# ADE7753Schematic-ATMEGA.net
KiCad netlist of a schematic drawn in EAGLE
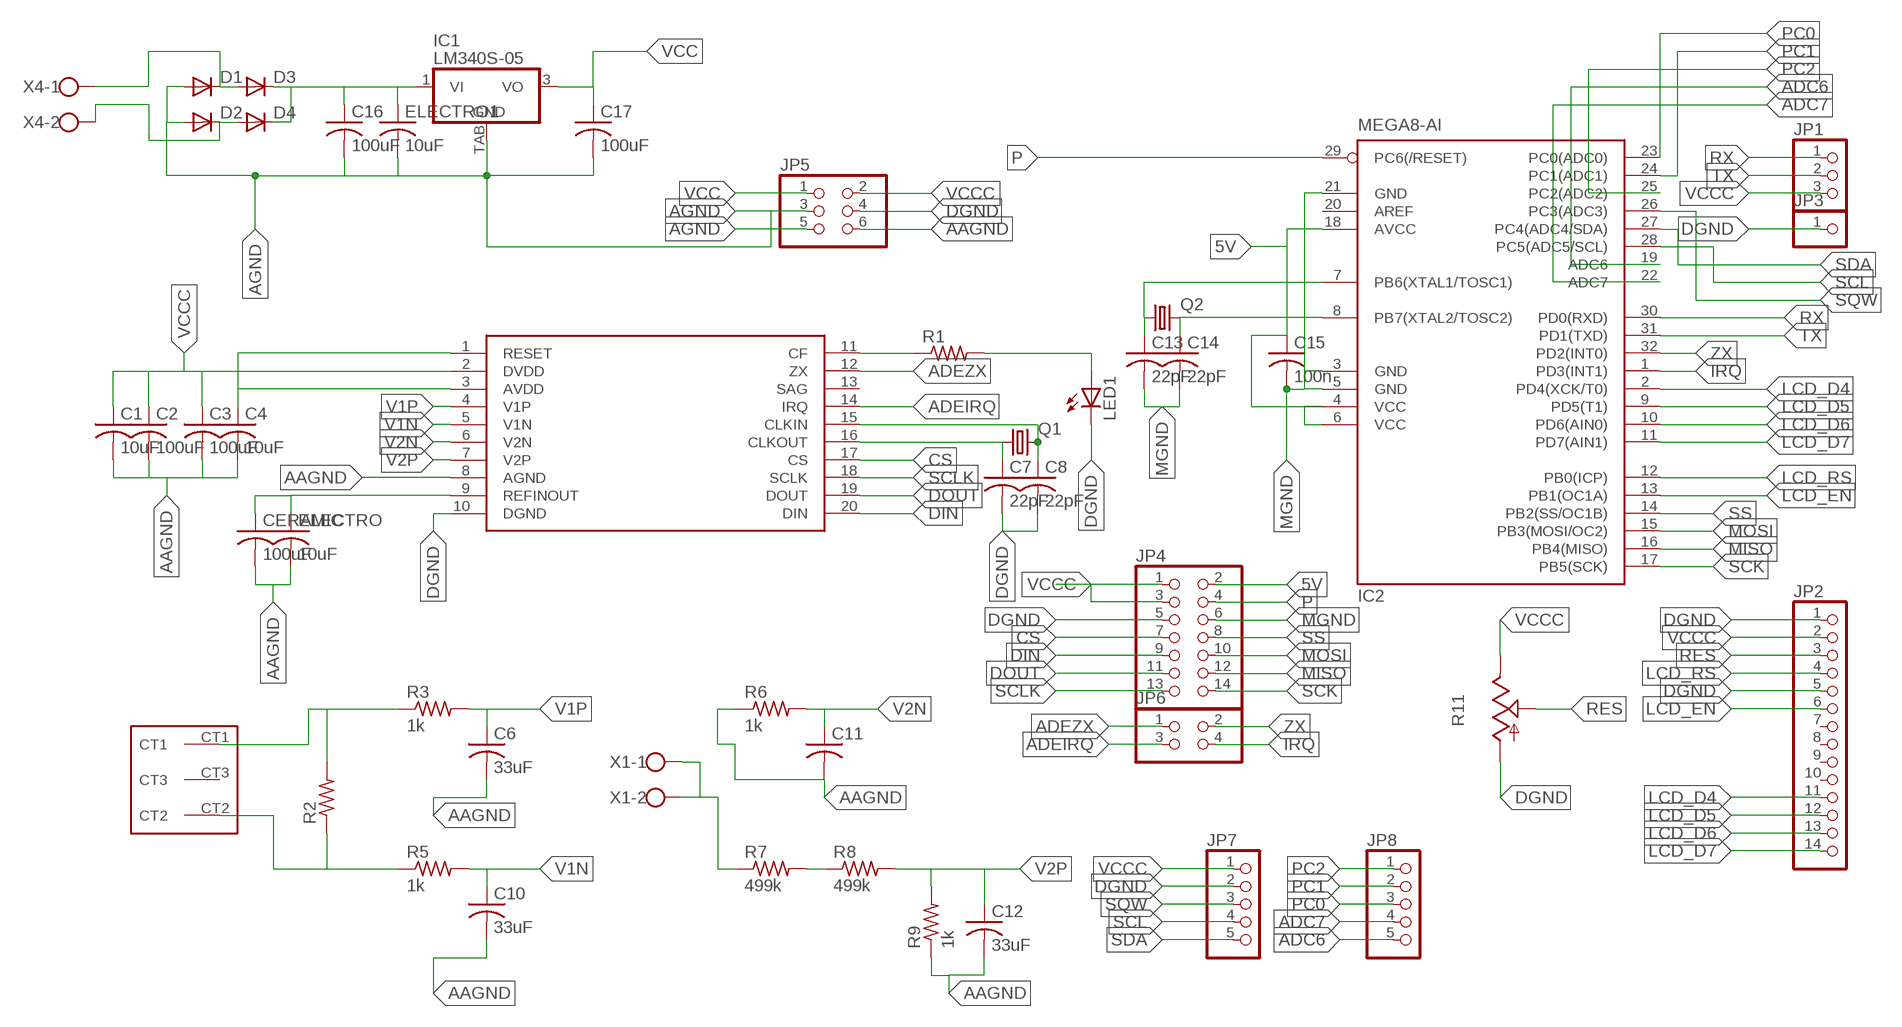
[diagram p0: schematic, sheet 1]

(export (version "E")
  (design (tool "Eeschema 10.0.6"))
  (components
    (comp (ref "C1")
      (value "10uF")
      (footprint "eagle-import:C025-030X050")
      (libsource (lib "eagle-import") (part "C-US025-030X050"))
    )
    (comp (ref "C2")
      (value "100uF")
      (footprint "eagle-import:C0603K")
      (libsource (lib "eagle-import") (part "C-USC0603K"))
    )
    (comp (ref "C3")
      (value "100uF")
      (footprint "eagle-import:C0603K")
      (libsource (lib "eagle-import") (part "C-USC0603K"))
    )
    (comp (ref "C4")
      (value "10uF")
      (footprint "eagle-import:C025-030X050")
      (libsource (lib "eagle-import") (part "C-US025-030X050"))
    )
    (comp (ref "C6")
      (value "33uF")
      (footprint "eagle-import:C0805K")
      (libsource (lib "eagle-import") (part "C-USC0805K"))
    )
    (comp (ref "C7")
      (value "22pF")
      (footprint "eagle-import:C0603K")
      (libsource (lib "eagle-import") (part "C-USC0603K"))
    )
    (comp (ref "C8")
      (value "22pF")
      (footprint "eagle-import:C0603K")
      (libsource (lib "eagle-import") (part "C-USC0603K"))
    )
    (comp (ref "C10")
      (value "33uF")
      (footprint "eagle-import:C0805K")
      (libsource (lib "eagle-import") (part "C-USC0805K"))
    )
    (comp (ref "C11")
      (value "C-USC0805K")
      (footprint "eagle-import:C0805K")
      (libsource (lib "eagle-import") (part "C-USC0805K"))
    )
    (comp (ref "C12")
      (value "33uF")
      (footprint "eagle-import:C0805K")
      (libsource (lib "eagle-import") (part "C-USC0805K"))
    )
    (comp (ref "C13")
      (value "22pF")
      (footprint "eagle-import:C0603K")
      (libsource (lib "eagle-import") (part "C-USC0603K"))
    )
    (comp (ref "C14")
      (value "22pF")
      (footprint "eagle-import:C0603K")
      (libsource (lib "eagle-import") (part "C-USC0603K"))
    )
    (comp (ref "C15")
      (value "100n")
      (footprint "eagle-import:C0603K")
      (libsource (lib "eagle-import") (part "C-USC0603K"))
    )
    (comp (ref "C16")
      (value "100uF")
      (footprint "eagle-import:C0603K")
      (libsource (lib "eagle-import") (part "C-USC0603K"))
    )
    (comp (ref "C17")
      (value "100uF")
      (footprint "eagle-import:C0603K")
      (libsource (lib "eagle-import") (part "C-USC0603K"))
    )
    (comp (ref "CERAMIC")
      (value "100uF")
      (footprint "eagle-import:C0603K")
      (libsource (lib "eagle-import") (part "C-USC0603K"))
    )
    (comp (ref "D1")
      (value "DIODE-SMB")
      (footprint "eagle-import:SMB")
      (libsource (lib "eagle-import") (part "DIODE-SMB"))
    )
    (comp (ref "D2")
      (value "DIODE-SMB")
      (footprint "eagle-import:SMB")
      (libsource (lib "eagle-import") (part "DIODE-SMB"))
    )
    (comp (ref "D3")
      (value "DIODE-SMB")
      (footprint "eagle-import:SMB")
      (libsource (lib "eagle-import") (part "DIODE-SMB"))
    )
    (comp (ref "D4")
      (value "DIODE-SMB")
      (footprint "eagle-import:SMB")
      (libsource (lib "eagle-import") (part "DIODE-SMB"))
    )
    (comp (ref "ELECTRO")
      (value "10uF")
      (footprint "eagle-import:C025-030X050")
      (libsource (lib "eagle-import") (part "C-US025-030X050"))
    )
    (comp (ref "ELECTRO1")
      (value "10uF")
      (footprint "eagle-import:C025-030X050")
      (libsource (lib "eagle-import") (part "C-US025-030X050"))
    )
    (comp (ref "IC1")
      (value "LM340S-05")
      (footprint "eagle-import:TO263-3")
      (libsource (lib "eagle-import") (part "LM340?-S05"))
    )
    (comp (ref "IC2")
      (value "MEGA8-AI")
      (footprint "eagle-import:TQFP32-08")
      (fields (field (name "MPN") "ATMEGA8-16AU"))
      (libsource (lib "eagle-import") (part "MEGA8-AI"))
    )
    (comp (ref "JP1")
      (value "PINHD-1X3CB")
      (footprint "eagle-import:1X03-CLEANBIG")
      (libsource (lib "eagle-import") (part "PINHD-1X3CB"))
    )
    (comp (ref "JP2")
      (value "PINHD-1X14-CB")
      (footprint "eagle-import:1X14-CB")
      (libsource (lib "eagle-import") (part "PINHD-1X14-CB"))
    )
    (comp (ref "JP3")
      (value "PINHD-1X1CB")
      (footprint "eagle-import:1X01-CLEANBIG")
      (libsource (lib "eagle-import") (part "PINHD-1X1CB"))
    )
    (comp (ref "JP4")
      (value "PINHD-2X7")
      (footprint "eagle-import:2X07")
      (libsource (lib "eagle-import") (part "PINHD-2X7"))
    )
    (comp (ref "JP5")
      (value "PINHD-2X3")
      (footprint "eagle-import:2X03")
      (libsource (lib "eagle-import") (part "PINHD-2X3"))
    )
    (comp (ref "JP6")
      (value "PINHD-2X2")
      (footprint "eagle-import:2X02")
      (libsource (lib "eagle-import") (part "PINHD-2X2"))
    )
    (comp (ref "JP7")
      (value "PINHD-1X5")
      (footprint "eagle-import:1X05")
      (libsource (lib "eagle-import") (part "PINHD-1X5"))
    )
    (comp (ref "JP8")
      (value "PINHD-1X5")
      (footprint "eagle-import:1X05")
      (libsource (lib "eagle-import") (part "PINHD-1X5"))
    )
    (comp (ref "LED1")
      (value "LEDCHIPLED_0805")
      (footprint "eagle-import:CHIPLED_0805")
      (libsource (lib "eagle-import") (part "LEDCHIPLED_0805"))
    )
    (comp (ref "Q1")
      (value "CRYSTALHC49S")
      (footprint "eagle-import:HC49_S")
      (libsource (lib "eagle-import") (part "CRYSTALHC49S"))
    )
    (comp (ref "Q2")
      (value "CRYSTALHC49UP")
      (footprint "eagle-import:HC49UP")
      (libsource (lib "eagle-import") (part "crystal_CRYSTALHC49UP"))
    )
    (comp (ref "R1")
      (value "R-US_R1206")
      (footprint "eagle-import:R1206")
      (libsource (lib "eagle-import") (part "R-US_R1206"))
    )
    (comp (ref "R2")
      (value "R-US_0309/12")
      (footprint "eagle-import:0309_12")
      (libsource (lib "eagle-import") (part "resistor_R-US_0309/12"))
    )
    (comp (ref "R3")
      (value "1k")
      (footprint "eagle-import:R1206")
      (libsource (lib "eagle-import") (part "R-US_R1206"))
    )
    (comp (ref "R5")
      (value "1k")
      (footprint "eagle-import:R1206")
      (libsource (lib "eagle-import") (part "R-US_R1206"))
    )
    (comp (ref "R6")
      (value "1k")
      (footprint "eagle-import:R1206")
      (libsource (lib "eagle-import") (part "R-US_R1206"))
    )
    (comp (ref "R7")
      (value "499k")
      (footprint "eagle-import:R1206")
      (libsource (lib "eagle-import") (part "R-US_R1206"))
    )
    (comp (ref "R8")
      (value "499k")
      (footprint "eagle-import:R1206")
      (libsource (lib "eagle-import") (part "R-US_R1206"))
    )
    (comp (ref "R9")
      (value "1k")
      (footprint "eagle-import:R1206")
      (libsource (lib "eagle-import") (part "R-US_R1206"))
    )
    (comp (ref "R11")
      (value "TRIM_US-RJ9W")
      (footprint "eagle-import:RJ9W")
      (libsource (lib "eagle-import") (part "TRIM_US-RJ9W"))
    )
    (comp (ref "U$1")
      (value "ADE7753")
      (footprint "eagle-import:SSOP20")
      (libsource (lib "eagle-import") (part "ADE7753"))
    )
    (comp (ref "U$2")
      (value "CURRENTXFORMER")
      (footprint "eagle-import:3PINS")
      (libsource (lib "eagle-import") (part "CURRENTXFORMER"))
    )
    (comp (ref "X1")
      (value "W239-302")
      (footprint "eagle-import:W239-302")
      (libsource (lib "eagle-import") (part "W239-302"))
    )
    (comp (ref "X4")
      (value "W237-102")
      (footprint "eagle-import:W237-102")
      (fields (field (name "MPN") "237-102"))
      (libsource (lib "eagle-import") (part "W237-102"))
    )
  )
  (nets
    (net (code "1") (name "5V") (class "Default")
      (node (ref "C15") (pin "1") (pinfunction "1_1") (pintype "passive"))
      (node (ref "IC2") (pin "18") (pinfunction "AVCC_18") (pintype "power_in"))
      (node (ref "IC2") (pin "4") (pinfunction "VCC_4") (pintype "power_in"))
      (node (ref "IC2") (pin "6") (pinfunction "VCC_6") (pintype "power_in"))
      (node (ref "JP4") (pin "2") (pinfunction "2_2") (pintype "passive"))
    )
    (net (code "2") (name "AAGND") (class "Default")
      (node (ref "C1") (pin "2") (pinfunction "2_2") (pintype "passive"))
      (node (ref "C10") (pin "2") (pinfunction "2_2") (pintype "passive"))
      (node (ref "C11") (pin "2") (pinfunction "2_2") (pintype "passive"))
      (node (ref "C12") (pin "2") (pinfunction "2_2") (pintype "passive"))
      (node (ref "C2") (pin "2") (pinfunction "2_2") (pintype "passive"))
      (node (ref "C3") (pin "2") (pinfunction "2_2") (pintype "passive"))
      (node (ref "C4") (pin "2") (pinfunction "2_2") (pintype "passive"))
      (node (ref "C6") (pin "2") (pinfunction "2_2") (pintype "passive"))
      (node (ref "CERAMIC") (pin "2") (pinfunction "2_2") (pintype "passive"))
      (node (ref "ELECTRO") (pin "2") (pinfunction "2_2") (pintype "passive"))
      (node (ref "JP5") (pin "6") (pinfunction "6_6") (pintype "passive"))
      (node (ref "R6") (pin "1") (pinfunction "1_1") (pintype "passive"))
      (node (ref "R9") (pin "1") (pinfunction "1_1") (pintype "passive"))
      (node (ref "U$1") (pin "8") (pinfunction "AGND_8") (pintype "bidirectional"))
    )
    (net (code "3") (name "ADC6") (class "Default")
      (node (ref "IC2") (pin "19") (pinfunction "ADC6_19") (pintype "bidirectional"))
      (node (ref "JP8") (pin "5") (pinfunction "5_5") (pintype "passive"))
    )
    (net (code "4") (name "ADC7") (class "Default")
      (node (ref "IC2") (pin "22") (pinfunction "ADC7_22") (pintype "bidirectional"))
      (node (ref "JP8") (pin "4") (pinfunction "4_4") (pintype "passive"))
    )
    (net (code "5") (name "ADEIRQ") (class "Default")
      (node (ref "JP6") (pin "3") (pinfunction "3_3") (pintype "passive"))
      (node (ref "U$1") (pin "14") (pinfunction "IRQ_14") (pintype "bidirectional"))
    )
    (net (code "6") (name "ADEZX") (class "Default")
      (node (ref "JP6") (pin "1") (pinfunction "1_1") (pintype "passive"))
      (node (ref "U$1") (pin "12") (pinfunction "ZX_12") (pintype "bidirectional"))
    )
    (net (code "7") (name "AGND") (class "Default")
      (node (ref "C16") (pin "2") (pinfunction "2_2") (pintype "passive"))
      (node (ref "C17") (pin "2") (pinfunction "2_2") (pintype "passive"))
      (node (ref "D1") (pin "A") (pinfunction "A_A") (pintype "passive"))
      (node (ref "D2") (pin "A") (pinfunction "A_A") (pintype "passive"))
      (node (ref "ELECTRO1") (pin "2") (pinfunction "2_2") (pintype "passive"))
      (node (ref "IC1") (pin "TAB") (pinfunction "GND_TAB") (pintype "passive"))
      (node (ref "JP5") (pin "3") (pinfunction "3_3") (pintype "passive"))
      (node (ref "JP5") (pin "5") (pinfunction "5_5") (pintype "passive"))
    )
    (net (code "8") (name "CS") (class "Default")
      (node (ref "JP4") (pin "7") (pinfunction "7_7") (pintype "passive"))
      (node (ref "U$1") (pin "17") (pinfunction "CS_17") (pintype "bidirectional"))
    )
    (net (code "9") (name "DGND") (class "Default")
      (node (ref "C7") (pin "2") (pinfunction "2_2") (pintype "passive"))
      (node (ref "C8") (pin "2") (pinfunction "2_2") (pintype "passive"))
      (node (ref "JP2") (pin "1") (pinfunction "1_1") (pintype "passive"))
      (node (ref "JP2") (pin "5") (pinfunction "5_5") (pintype "passive"))
      (node (ref "JP3") (pin "1") (pinfunction "1_1") (pintype "passive"))
      (node (ref "JP4") (pin "5") (pinfunction "5_5") (pintype "passive"))
      (node (ref "JP5") (pin "4") (pinfunction "4_4") (pintype "passive"))
      (node (ref "JP7") (pin "2") (pinfunction "2_2") (pintype "passive"))
      (node (ref "LED1") (pin "C") (pinfunction "C_C") (pintype "passive"))
      (node (ref "R11") (pin "A") (pinfunction "A_A") (pintype "passive"))
      (node (ref "U$1") (pin "10") (pinfunction "DGND_10") (pintype "bidirectional"))
    )
    (net (code "10") (name "DIN") (class "Default")
      (node (ref "JP4") (pin "9") (pinfunction "9_9") (pintype "passive"))
      (node (ref "U$1") (pin "20") (pinfunction "DIN_20") (pintype "bidirectional"))
    )
    (net (code "11") (name "DOUT") (class "Default")
      (node (ref "JP4") (pin "11") (pinfunction "11_11") (pintype "passive"))
      (node (ref "U$1") (pin "19") (pinfunction "DOUT_19") (pintype "bidirectional"))
    )
    (net (code "12") (name "IRQ") (class "Default")
      (node (ref "IC2") (pin "1") (pinfunction "PD3(INT1)_1") (pintype "bidirectional"))
      (node (ref "JP6") (pin "4") (pinfunction "4_4") (pintype "passive"))
    )
    (net (code "13") (name "LCD_D4") (class "Default")
      (node (ref "IC2") (pin "2") (pinfunction "PD4(XCK/T0)_2") (pintype "bidirectional"))
      (node (ref "JP2") (pin "11") (pinfunction "11_11") (pintype "passive"))
    )
    (net (code "14") (name "LCD_D5") (class "Default")
      (node (ref "IC2") (pin "9") (pinfunction "PD5(T1)_9") (pintype "bidirectional"))
      (node (ref "JP2") (pin "12") (pinfunction "12_12") (pintype "passive"))
    )
    (net (code "15") (name "LCD_D6") (class "Default")
      (node (ref "IC2") (pin "10") (pinfunction "PD6(AIN0)_10") (pintype "bidirectional"))
      (node (ref "JP2") (pin "13") (pinfunction "13_13") (pintype "passive"))
    )
    (net (code "16") (name "LCD_D7") (class "Default")
      (node (ref "IC2") (pin "11") (pinfunction "PD7(AIN1)_11") (pintype "bidirectional"))
      (node (ref "JP2") (pin "14") (pinfunction "14_14") (pintype "passive"))
    )
    (net (code "17") (name "LCD_EN") (class "Default")
      (node (ref "IC2") (pin "13") (pinfunction "PB1(OC1A)_13") (pintype "bidirectional"))
      (node (ref "JP2") (pin "6") (pinfunction "6_6") (pintype "passive"))
    )
    (net (code "18") (name "LCD_RS") (class "Default")
      (node (ref "IC2") (pin "12") (pinfunction "PB0(ICP)_12") (pintype "bidirectional"))
      (node (ref "JP2") (pin "4") (pinfunction "4_4") (pintype "passive"))
    )
    (net (code "19") (name "MGND") (class "Default")
      (node (ref "C13") (pin "2") (pinfunction "2_2") (pintype "passive"))
      (node (ref "C14") (pin "2") (pinfunction "2_2") (pintype "passive"))
      (node (ref "C15") (pin "2") (pinfunction "2_2") (pintype "passive"))
      (node (ref "IC2") (pin "21") (pinfunction "GND_21") (pintype "power_in"))
      (node (ref "IC2") (pin "3") (pinfunction "GND_3") (pintype "power_in"))
      (node (ref "IC2") (pin "5") (pinfunction "GND_5") (pintype "power_in"))
      (node (ref "JP4") (pin "6") (pinfunction "6_6") (pintype "passive"))
    )
    (net (code "20") (name "MISO") (class "Default")
      (node (ref "IC2") (pin "16") (pinfunction "PB4(MISO)_16") (pintype "bidirectional"))
      (node (ref "JP4") (pin "12") (pinfunction "12_12") (pintype "passive"))
    )
    (net (code "21") (name "MOSI") (class "Default")
      (node (ref "IC2") (pin "15") (pinfunction "PB3(MOSI/OC2)_15") (pintype "bidirectional"))
      (node (ref "JP4") (pin "10") (pinfunction "10_10") (pintype "passive"))
    )
    (net (code "22") (name "Net-(IC1-VI)") (class "Default")
      (node (ref "C16") (pin "1") (pinfunction "1_1") (pintype "passive"))
      (node (ref "D3") (pin "C") (pinfunction "C_C") (pintype "passive"))
      (node (ref "D4") (pin "C") (pinfunction "C_C") (pintype "passive"))
      (node (ref "ELECTRO1") (pin "1") (pinfunction "1_1") (pintype "passive"))
      (node (ref "IC1") (pin "1") (pinfunction "VI_1") (pintype "input"))
    )
    (net (code "23") (name "Net-(IC2-PB6(XTAL1{slash}TOSC1))") (class "Default")
      (node (ref "C13") (pin "1") (pinfunction "1_1") (pintype "passive"))
      (node (ref "IC2") (pin "7") (pinfunction "PB6(XTAL1/TOSC1)_7") (pintype "bidirectional"))
      (node (ref "Q2") (pin "1") (pinfunction "1_1") (pintype "passive"))
    )
    (net (code "24") (name "Net-(IC2-PB7(XTAL2{slash}TOSC2))") (class "Default")
      (node (ref "C14") (pin "1") (pinfunction "1_1") (pintype "passive"))
      (node (ref "IC2") (pin "8") (pinfunction "PB7(XTAL2/TOSC2)_8") (pintype "bidirectional"))
      (node (ref "Q2") (pin "2") (pinfunction "2_2") (pintype "passive"))
    )
    (net (code "25") (name "Net-(LED1-PadA)") (class "Default")
      (node (ref "LED1") (pin "A") (pinfunction "A_A") (pintype "passive"))
      (node (ref "R1") (pin "2") (pinfunction "2_2") (pintype "passive"))
    )
    (net (code "26") (name "Net-(R2-Pad1)") (class "Default")
      (node (ref "R2") (pin "1") (pinfunction "1_1") (pintype "passive"))
      (node (ref "R5") (pin "1") (pinfunction "1_1") (pintype "passive"))
      (node (ref "U$2") (pin "CT2") (pinfunction "CT2_CT2") (pintype "bidirectional"))
    )
    (net (code "27") (name "Net-(R2-Pad2)") (class "Default")
      (node (ref "R2") (pin "2") (pinfunction "2_2") (pintype "passive"))
      (node (ref "R3") (pin "1") (pinfunction "1_1") (pintype "passive"))
      (node (ref "U$2") (pin "CT1") (pinfunction "CT1_CT1") (pintype "bidirectional"))
    )
    (net (code "28") (name "Net-(R7-Pad2)") (class "Default")
      (node (ref "R7") (pin "2") (pinfunction "2_2") (pintype "passive"))
      (node (ref "R8") (pin "1") (pinfunction "1_1") (pintype "passive"))
    )
    (net (code "29") (name "Net-(U$1-CF)") (class "Default")
      (node (ref "R1") (pin "1") (pinfunction "1_1") (pintype "passive"))
      (node (ref "U$1") (pin "11") (pinfunction "CF_11") (pintype "bidirectional"))
    )
    (net (code "30") (name "Net-(U$1-CLKIN)") (class "Default")
      (node (ref "C8") (pin "1") (pinfunction "1_1") (pintype "passive"))
      (node (ref "Q1") (pin "2") (pinfunction "2_2") (pintype "passive"))
      (node (ref "U$1") (pin "15") (pinfunction "CLKIN_15") (pintype "bidirectional"))
    )
    (net (code "31") (name "Net-(U$1-CLKOUT)") (class "Default")
      (node (ref "C7") (pin "1") (pinfunction "1_1") (pintype "passive"))
      (node (ref "Q1") (pin "1") (pinfunction "1_1") (pintype "passive"))
      (node (ref "U$1") (pin "16") (pinfunction "CLKOUT_16") (pintype "bidirectional"))
    )
    (net (code "32") (name "Net-(U$1-REFINOUT)") (class "Default")
      (node (ref "CERAMIC") (pin "1") (pinfunction "1_1") (pintype "passive"))
      (node (ref "ELECTRO") (pin "1") (pinfunction "1_1") (pintype "passive"))
      (node (ref "U$1") (pin "9") (pinfunction "REFINOUT_9") (pintype "bidirectional"))
    )
    (net (code "33") (name "Net-(X1A-KL)") (class "Default")
      (node (ref "R7") (pin "1") (pinfunction "1_1") (pintype "passive"))
      (node (ref "X1") (pin "1") (pinfunction "KL_1") (pintype "passive"))
      (node (ref "X1") (pin "2") (pinfunction "KL_2") (pintype "passive"))
    )
    (net (code "34") (name "Net-(X4A-KL)") (class "Default")
      (node (ref "D1") (pin "C") (pinfunction "C_C") (pintype "passive"))
      (node (ref "D3") (pin "A") (pinfunction "A_A") (pintype "passive"))
      (node (ref "X4") (pin "1") (pinfunction "KL_1") (pintype "passive"))
    )
    (net (code "35") (name "Net-(X4B-KL)") (class "Default")
      (node (ref "D2") (pin "C") (pinfunction "C_C") (pintype "passive"))
      (node (ref "D4") (pin "A") (pinfunction "A_A") (pintype "passive"))
      (node (ref "X4") (pin "2") (pinfunction "KL_2") (pintype "passive"))
    )
    (net (code "36") (name "P") (class "Default")
      (node (ref "IC2") (pin "29") (pinfunction "PC6(/RESET)_29") (pintype "bidirectional"))
      (node (ref "JP4") (pin "4") (pinfunction "4_4") (pintype "passive"))
    )
    (net (code "37") (name "PC0") (class "Default")
      (node (ref "IC2") (pin "23") (pinfunction "PC0(ADC0)_23") (pintype "bidirectional"))
      (node (ref "JP8") (pin "3") (pinfunction "3_3") (pintype "passive"))
    )
    (net (code "38") (name "PC1") (class "Default")
      (node (ref "IC2") (pin "24") (pinfunction "PC1(ADC1)_24") (pintype "bidirectional"))
      (node (ref "JP8") (pin "2") (pinfunction "2_2") (pintype "passive"))
    )
    (net (code "39") (name "PC2") (class "Default")
      (node (ref "IC2") (pin "25") (pinfunction "PC2(ADC2)_25") (pintype "bidirectional"))
      (node (ref "JP8") (pin "1") (pinfunction "1_1") (pintype "passive"))
    )
    (net (code "40") (name "RES") (class "Default")
      (node (ref "JP2") (pin "3") (pinfunction "3_3") (pintype "passive"))
      (node (ref "R11") (pin "S") (pinfunction "S_S") (pintype "passive"))
    )
    (net (code "41") (name "RX") (class "Default")
      (node (ref "IC2") (pin "30") (pinfunction "PD0(RXD)_30") (pintype "bidirectional"))
      (node (ref "JP1") (pin "1") (pinfunction "1_1") (pintype "passive"))
    )
    (net (code "42") (name "SCK") (class "Default")
      (node (ref "IC2") (pin "17") (pinfunction "PB5(SCK)_17") (pintype "bidirectional"))
      (node (ref "JP4") (pin "14") (pinfunction "14_14") (pintype "passive"))
    )
    (net (code "43") (name "SCL") (class "Default")
      (node (ref "IC2") (pin "28") (pinfunction "PC5(ADC5/SCL)_28") (pintype "bidirectional"))
      (node (ref "JP7") (pin "4") (pinfunction "4_4") (pintype "passive"))
    )
    (net (code "44") (name "SCLK") (class "Default")
      (node (ref "JP4") (pin "13") (pinfunction "13_13") (pintype "passive"))
      (node (ref "U$1") (pin "18") (pinfunction "SCLK_18") (pintype "bidirectional"))
    )
    (net (code "45") (name "SDA") (class "Default")
      (node (ref "IC2") (pin "27") (pinfunction "PC4(ADC4/SDA)_27") (pintype "bidirectional"))
      (node (ref "JP7") (pin "5") (pinfunction "5_5") (pintype "passive"))
    )
    (net (code "46") (name "SQW") (class "Default")
      (node (ref "IC2") (pin "26") (pinfunction "PC3(ADC3)_26") (pintype "bidirectional"))
      (node (ref "JP7") (pin "3") (pinfunction "3_3") (pintype "passive"))
    )
    (net (code "47") (name "SS") (class "Default")
      (node (ref "IC2") (pin "14") (pinfunction "PB2(SS/OC1B)_14") (pintype "bidirectional"))
      (node (ref "JP4") (pin "8") (pinfunction "8_8") (pintype "passive"))
    )
    (net (code "48") (name "TX") (class "Default")
      (node (ref "IC2") (pin "31") (pinfunction "PD1(TXD)_31") (pintype "bidirectional"))
      (node (ref "JP1") (pin "2") (pinfunction "2_2") (pintype "passive"))
    )
    (net (code "49") (name "V1N") (class "Default")
      (node (ref "C10") (pin "1") (pinfunction "1_1") (pintype "passive"))
      (node (ref "R5") (pin "2") (pinfunction "2_2") (pintype "passive"))
      (node (ref "U$1") (pin "5") (pinfunction "V1N_5") (pintype "bidirectional"))
    )
    (net (code "50") (name "V1P") (class "Default")
      (node (ref "C6") (pin "1") (pinfunction "1_1") (pintype "passive"))
      (node (ref "R3") (pin "2") (pinfunction "2_2") (pintype "passive"))
      (node (ref "U$1") (pin "4") (pinfunction "V1P_4") (pintype "bidirectional"))
    )
    (net (code "51") (name "V2N") (class "Default")
      (node (ref "C11") (pin "1") (pinfunction "1_1") (pintype "passive"))
      (node (ref "R6") (pin "2") (pinfunction "2_2") (pintype "passive"))
      (node (ref "U$1") (pin "6") (pinfunction "V2N_6") (pintype "bidirectional"))
    )
    (net (code "52") (name "V2P") (class "Default")
      (node (ref "C12") (pin "1") (pinfunction "1_1") (pintype "passive"))
      (node (ref "R8") (pin "2") (pinfunction "2_2") (pintype "passive"))
      (node (ref "R9") (pin "2") (pinfunction "2_2") (pintype "passive"))
      (node (ref "U$1") (pin "7") (pinfunction "V2P_7") (pintype "bidirectional"))
    )
    (net (code "53") (name "VCC") (class "Default")
      (node (ref "C17") (pin "1") (pinfunction "1_1") (pintype "passive"))
      (node (ref "IC1") (pin "3") (pinfunction "VO_3") (pintype "passive"))
      (node (ref "JP5") (pin "1") (pinfunction "1_1") (pintype "passive"))
    )
    (net (code "54") (name "VCCC") (class "Default")
      (node (ref "C1") (pin "1") (pinfunction "1_1") (pintype "passive"))
      (node (ref "C2") (pin "1") (pinfunction "1_1") (pintype "passive"))
      (node (ref "C3") (pin "1") (pinfunction "1_1") (pintype "passive"))
      (node (ref "C4") (pin "1") (pinfunction "1_1") (pintype "passive"))
      (node (ref "JP1") (pin "3") (pinfunction "3_3") (pintype "passive"))
      (node (ref "JP2") (pin "2") (pinfunction "2_2") (pintype "passive"))
      (node (ref "JP4") (pin "1") (pinfunction "1_1") (pintype "passive"))
      (node (ref "JP4") (pin "3") (pinfunction "3_3") (pintype "passive"))
      (node (ref "JP5") (pin "2") (pinfunction "2_2") (pintype "passive"))
      (node (ref "JP7") (pin "1") (pinfunction "1_1") (pintype "passive"))
      (node (ref "R11") (pin "E") (pinfunction "E_E") (pintype "passive"))
      (node (ref "U$1") (pin "1") (pinfunction "RESET_1") (pintype "bidirectional"))
      (node (ref "U$1") (pin "2") (pinfunction "DVDD_2") (pintype "bidirectional"))
      (node (ref "U$1") (pin "3") (pinfunction "AVDD_3") (pintype "bidirectional"))
    )
    (net (code "55") (name "ZX") (class "Default")
      (node (ref "IC2") (pin "32") (pinfunction "PD2(INT0)_32") (pintype "bidirectional"))
      (node (ref "JP6") (pin "2") (pinfunction "2_2") (pintype "passive"))
    )
    (net (code "56") (name "unconnected-(IC2-AREF-Pad20)") (class "Default")
      (node (ref "IC2") (pin "20") (pinfunction "AREF_20") (pintype "passive"))
    )
    (net (code "57") (name "unconnected-(JP2-Pad7)") (class "Default")
      (node (ref "JP2") (pin "7") (pinfunction "7_7") (pintype "passive"))
    )
    (net (code "58") (name "unconnected-(JP2-Pad8)") (class "Default")
      (node (ref "JP2") (pin "8") (pinfunction "8_8") (pintype "passive"))
    )
    (net (code "59") (name "unconnected-(JP2-Pad9)") (class "Default")
      (node (ref "JP2") (pin "9") (pinfunction "9_9") (pintype "passive"))
    )
    (net (code "60") (name "unconnected-(JP2-Pad10)") (class "Default")
      (node (ref "JP2") (pin "10") (pinfunction "10_10") (pintype "passive"))
    )
    (net (code "61") (name "unconnected-(U$1-SAG-Pad13)") (class "Default")
      (node (ref "U$1") (pin "13") (pinfunction "SAG_13") (pintype "bidirectional"))
    )
    (net (code "62") (name "unconnected-(U$2-PadCT3)") (class "Default")
      (node (ref "U$2") (pin "CT3") (pinfunction "CT3_CT3") (pintype "bidirectional"))
    )
  )
)
